# Diver_Marker_AA.net
KiCad netlist of a schematic drawn in EAGLE
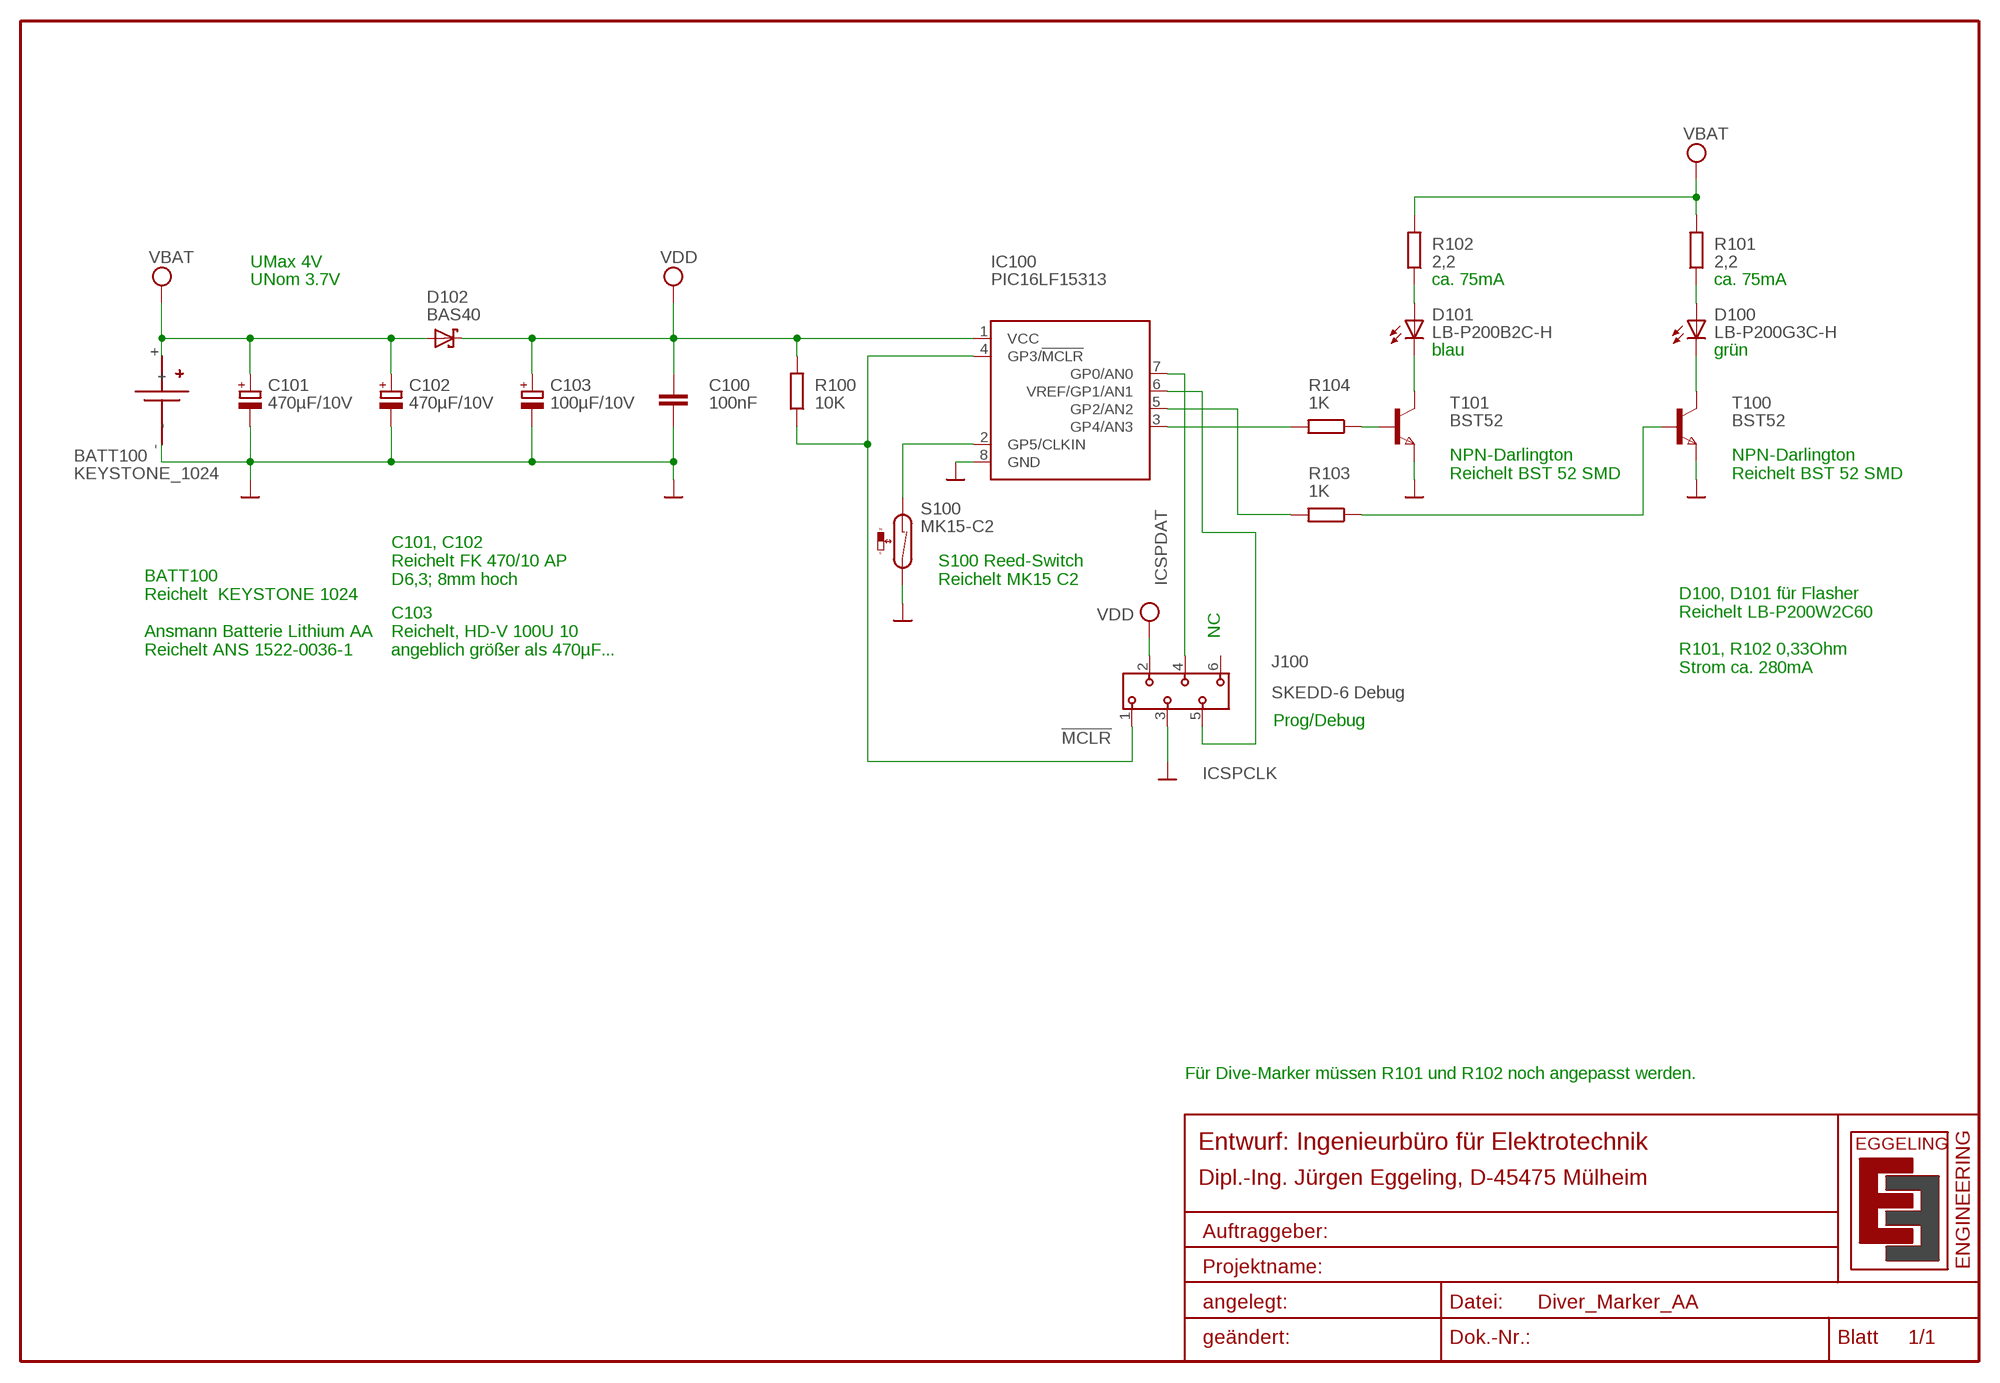
[diagram p0: schematic, sheet 1]

(export (version "E")
  (design (tool "Eeschema 10.0.6"))
  (components
    (comp (ref "BATT100")
      (value "KEYSTONE_1024")
      (footprint "eagle-import:KEYSTONE_1024_AA_SMD")
      (libsource (lib "eagle-import") (part "KEYSTONE_1024_AA_SMD"))
    )
    (comp (ref "C100")
      (value "100nF")
      (footprint "eagle-import:C0805")
      (libsource (lib "eagle-import") (part "C-EUC0805"))
    )
    (comp (ref "C101")
      (value "470µF/10V")
      (footprint "eagle-import:153CLV-0605")
      (libsource (lib "eagle-import") (part "CPOL-EU153CLV-0605"))
    )
    (comp (ref "C102")
      (value "470µF/10V")
      (footprint "eagle-import:153CLV-0605")
      (libsource (lib "eagle-import") (part "CPOL-EU153CLV-0605"))
    )
    (comp (ref "C103")
      (value "100µF/10V")
      (footprint "eagle-import:153CLV-0605")
      (libsource (lib "eagle-import") (part "CPOL-EU153CLV-0605"))
    )
    (comp (ref "D100")
      (value "LB-P200G3C-H")
      (footprint "eagle-import:Z-POWER-LED-PCB-TYPE")
      (libsource (lib "eagle-import") (part "Z-POWER-LED"))
    )
    (comp (ref "D101")
      (value "LB-P200B2C-H")
      (footprint "eagle-import:Z-POWER-LED-PCB-TYPE")
      (libsource (lib "eagle-import") (part "Z-POWER-LED"))
    )
    (comp (ref "D102")
      (value "BAS40")
      (footprint "eagle-import:SOT23")
      (libsource (lib "eagle-import") (part "BAS40"))
    )
    (comp (ref "IC100")
      (value "PIC16LF15313")
      (footprint "eagle-import:SO-08")
      (fields (field (name "MF") "MICROCHIP") (field (name "MPN") "PIC12F675-E/SN"))
      (libsource (lib "eagle-import") (part "PIC12F675SN"))
    )
    (comp (ref "J100")
      (value "SKEDD-6 Debug")
      (footprint "eagle-import:490107670612_DEBUGGING")
      (libsource (lib "eagle-import") (part "490107670612_DEBUGGING"))
    )
    (comp (ref "R100")
      (value "10K")
      (footprint "eagle-import:R0805")
      (libsource (lib "eagle-import") (part "R-EU_R0805"))
    )
    (comp (ref "R101")
      (value "2,2")
      (footprint "eagle-import:R0805")
      (libsource (lib "eagle-import") (part "R-EU_R0805"))
    )
    (comp (ref "R102")
      (value "2,2")
      (footprint "eagle-import:R0805")
      (libsource (lib "eagle-import") (part "R-EU_R0805"))
    )
    (comp (ref "R103")
      (value "1K")
      (footprint "eagle-import:R0805")
      (libsource (lib "eagle-import") (part "R-EU_R0805"))
    )
    (comp (ref "R104")
      (value "1K")
      (footprint "eagle-import:R0805")
      (libsource (lib "eagle-import") (part "R-EU_R0805"))
    )
    (comp (ref "S100")
      (value "MK15-C2")
      (footprint "eagle-import:MK15")
      (fields (field (name "MF") "MEDER") (field (name "MPN") "MK15-C-2"))
      (libsource (lib "eagle-import") (part "REED-SWITCH-MK15-C2"))
    )
    (comp (ref "T100")
      (value "BST52")
      (footprint "eagle-import:SOT89")
      (fields (field (name "MPN") "DSS4540X-13"))
      (libsource (lib "eagle-import") (part "NPNSOT89"))
    )
    (comp (ref "T101")
      (value "BST52")
      (footprint "eagle-import:SOT89")
      (fields (field (name "MPN") "DSS4540X-13"))
      (libsource (lib "eagle-import") (part "NPNSOT89"))
    )
  )
  (nets
    (net (code "1") (name "/ICSPCLK") (class "Default")
      (node (ref "IC100") (pin "6") (pinfunction "VREF/GP1/AN1_6") (pintype "bidirectional"))
      (node (ref "J100") (pin "5") (pinfunction "5_5") (pintype "passive"))
    )
    (net (code "2") (name "/ICSPDAT") (class "Default")
      (node (ref "IC100") (pin "7") (pinfunction "GP0/AN0_7") (pintype "bidirectional"))
      (node (ref "J100") (pin "4") (pinfunction "4_4") (pintype "passive"))
    )
    (net (code "3") (name "/~{MCLR}") (class "Default")
      (node (ref "IC100") (pin "4") (pinfunction "GP3/~{MCLR}_4") (pintype "input"))
      (node (ref "J100") (pin "1") (pinfunction "1_1") (pintype "passive"))
      (node (ref "R100") (pin "1") (pinfunction "1_1") (pintype "passive"))
    )
    (net (code "4") (name "GND") (class "Default")
      (node (ref "BATT100") (pin "-") (pinfunction "-_-") (pintype "bidirectional"))
      (node (ref "C100") (pin "2") (pinfunction "2_2") (pintype "passive"))
      (node (ref "C101") (pin "-") (pinfunction "-_-") (pintype "passive"))
      (node (ref "C102") (pin "-") (pinfunction "-_-") (pintype "passive"))
      (node (ref "C103") (pin "-") (pinfunction "-_-") (pintype "passive"))
      (node (ref "IC100") (pin "8") (pinfunction "GND_8") (pintype "power_in"))
      (node (ref "J100") (pin "3") (pinfunction "3_3") (pintype "passive"))
      (node (ref "S100") (pin "2") (pinfunction "2_2") (pintype "passive"))
      (node (ref "T100") (pin "3") (pinfunction "E_3") (pintype "passive"))
      (node (ref "T101") (pin "3") (pinfunction "E_3") (pintype "passive"))
    )
    (net (code "5") (name "Net-(D100-PadA)") (class "Default")
      (node (ref "D100") (pin "A") (pinfunction "A_A") (pintype "passive"))
      (node (ref "R101") (pin "1") (pinfunction "1_1") (pintype "passive"))
    )
    (net (code "6") (name "Net-(D100-PadC)") (class "Default")
      (node (ref "D100") (pin "C") (pinfunction "C_C") (pintype "passive"))
      (node (ref "T100") (pin "2") (pinfunction "C_2") (pintype "passive"))
      (node (ref "T100") (pin "2@1") (pinfunction "C_2@1") (pintype "passive"))
    )
    (net (code "7") (name "Net-(D101-PadA)") (class "Default")
      (node (ref "D101") (pin "A") (pinfunction "A_A") (pintype "passive"))
      (node (ref "R102") (pin "1") (pinfunction "1_1") (pintype "passive"))
    )
    (net (code "8") (name "Net-(D101-PadC)") (class "Default")
      (node (ref "D101") (pin "C") (pinfunction "C_C") (pintype "passive"))
      (node (ref "T101") (pin "2") (pinfunction "C_2") (pintype "passive"))
      (node (ref "T101") (pin "2@1") (pinfunction "C_2@1") (pintype "passive"))
    )
    (net (code "9") (name "Net-(IC100-GP2{slash}AN2)") (class "Default")
      (node (ref "IC100") (pin "5") (pinfunction "GP2/AN2_5") (pintype "bidirectional"))
      (node (ref "R103") (pin "2") (pinfunction "2_2") (pintype "passive"))
    )
    (net (code "10") (name "Net-(IC100-GP4{slash}AN3)") (class "Default")
      (node (ref "IC100") (pin "3") (pinfunction "GP4/AN3_3") (pintype "bidirectional"))
      (node (ref "R104") (pin "2") (pinfunction "2_2") (pintype "passive"))
    )
    (net (code "11") (name "Net-(IC100-GP5{slash}CLKIN)") (class "Default")
      (node (ref "IC100") (pin "2") (pinfunction "GP5/CLKIN_2") (pintype "bidirectional"))
      (node (ref "S100") (pin "1") (pinfunction "1_1") (pintype "passive"))
    )
    (net (code "12") (name "Net-(T100-B)") (class "Default")
      (node (ref "R103") (pin "1") (pinfunction "1_1") (pintype "passive"))
      (node (ref "T100") (pin "1") (pinfunction "B_1") (pintype "passive"))
    )
    (net (code "13") (name "Net-(T101-B)") (class "Default")
      (node (ref "R104") (pin "1") (pinfunction "1_1") (pintype "passive"))
      (node (ref "T101") (pin "1") (pinfunction "B_1") (pintype "passive"))
    )
    (net (code "14") (name "VBAT") (class "Default")
      (node (ref "BATT100") (pin "+") (pinfunction "+_+") (pintype "bidirectional"))
      (node (ref "C101") (pin "+") (pinfunction "+_+") (pintype "passive"))
      (node (ref "C102") (pin "+") (pinfunction "+_+") (pintype "passive"))
      (node (ref "D102") (pin "1") (pinfunction "A_1") (pintype "passive"))
      (node (ref "R101") (pin "2") (pinfunction "2_2") (pintype "passive"))
      (node (ref "R102") (pin "2") (pinfunction "2_2") (pintype "passive"))
    )
    (net (code "15") (name "VDD") (class "Default")
      (node (ref "C100") (pin "1") (pinfunction "1_1") (pintype "passive"))
      (node (ref "C103") (pin "+") (pinfunction "+_+") (pintype "passive"))
      (node (ref "D102") (pin "3") (pinfunction "C_3") (pintype "passive"))
      (node (ref "IC100") (pin "1") (pinfunction "VCC_1") (pintype "power_in"))
      (node (ref "J100") (pin "2") (pinfunction "2_2") (pintype "passive"))
      (node (ref "R100") (pin "2") (pinfunction "2_2") (pintype "passive"))
    )
    (net (code "16") (name "unconnected-(J100-Pad6)") (class "Default")
      (node (ref "J100") (pin "6") (pinfunction "6_6") (pintype "passive"))
    )
  )
)
